# Board.net
KiCad netlist of a schematic drawn in EAGLE
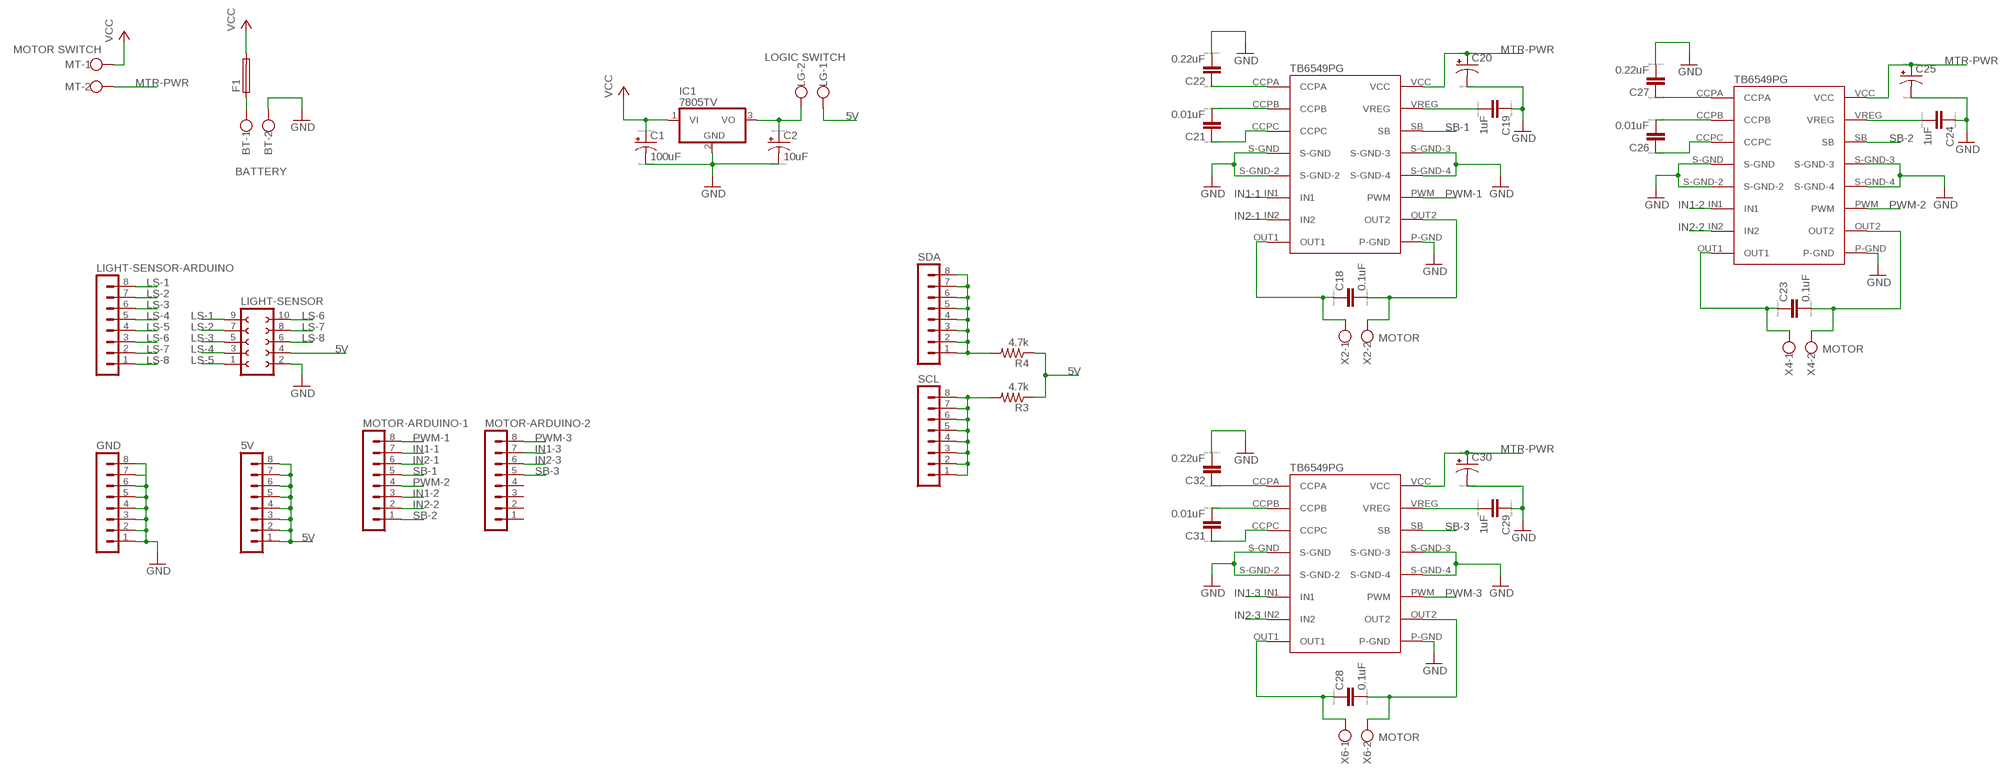
[diagram p0: schematic, sheet 1]

(export (version "E")
  (design (tool "Eeschema 10.0.6"))
  (components
    (comp (ref "5V")
      (value "MA08-1")
      (footprint "eagle-import:MA08-1")
      (libsource (lib "eagle-import") (part "MA08-1"))
    )
    (comp (ref "BT")
      (value "W237-102")
      (footprint "eagle-import:W237-102")
      (fields (field (name "MPN") "237-102"))
      (libsource (lib "eagle-import") (part "W237-102"))
    )
    (comp (ref "C1")
      (value "100uF")
      (footprint "eagle-import:E3,5-8")
      (libsource (lib "eagle-import") (part "CPOL-USE3.5-8"))
    )
    (comp (ref "C2")
      (value "10uF")
      (footprint "eagle-import:E3,5-8")
      (libsource (lib "eagle-import") (part "CPOL-USE3.5-8"))
    )
    (comp (ref "C18")
      (value "0.1uF")
      (footprint "eagle-import:YC7B5")
      (libsource (lib "eagle-import") (part "CYYC7B5"))
    )
    (comp (ref "C19")
      (value "1uF")
      (footprint "eagle-import:YC7B5")
      (libsource (lib "eagle-import") (part "CYYC7B5"))
    )
    (comp (ref "C20")
      (value "CPOL-USE3.5-8")
      (footprint "eagle-import:E3,5-8")
      (libsource (lib "eagle-import") (part "CPOL-USE3.5-8"))
    )
    (comp (ref "C21")
      (value "0.01uF")
      (footprint "eagle-import:YC7B5")
      (libsource (lib "eagle-import") (part "CYYC7B5"))
    )
    (comp (ref "C22")
      (value "0.22uF")
      (footprint "eagle-import:YC7B5")
      (libsource (lib "eagle-import") (part "CYYC7B5"))
    )
    (comp (ref "C23")
      (value "0.1uF")
      (footprint "eagle-import:YC7B5")
      (libsource (lib "eagle-import") (part "CYYC7B5"))
    )
    (comp (ref "C24")
      (value "1uF")
      (footprint "eagle-import:YC7B5")
      (libsource (lib "eagle-import") (part "CYYC7B5"))
    )
    (comp (ref "C25")
      (value "CPOL-USE3.5-8")
      (footprint "eagle-import:E3,5-8")
      (libsource (lib "eagle-import") (part "CPOL-USE3.5-8"))
    )
    (comp (ref "C26")
      (value "0.01uF")
      (footprint "eagle-import:YC7B5")
      (libsource (lib "eagle-import") (part "CYYC7B5"))
    )
    (comp (ref "C27")
      (value "0.22uF")
      (footprint "eagle-import:YC7B5")
      (libsource (lib "eagle-import") (part "CYYC7B5"))
    )
    (comp (ref "C28")
      (value "0.1uF")
      (footprint "eagle-import:YC7B5")
      (libsource (lib "eagle-import") (part "CYYC7B5"))
    )
    (comp (ref "C29")
      (value "1uF")
      (footprint "eagle-import:YC7B5")
      (libsource (lib "eagle-import") (part "CYYC7B5"))
    )
    (comp (ref "C30")
      (value "CPOL-USE3.5-8")
      (footprint "eagle-import:E3,5-8")
      (libsource (lib "eagle-import") (part "CPOL-USE3.5-8"))
    )
    (comp (ref "C31")
      (value "0.01uF")
      (footprint "eagle-import:YC7B5")
      (libsource (lib "eagle-import") (part "CYYC7B5"))
    )
    (comp (ref "C32")
      (value "0.22uF")
      (footprint "eagle-import:YC7B5")
      (libsource (lib "eagle-import") (part "CYYC7B5"))
    )
    (comp (ref "F1")
      (value "GSH15")
      (footprint "eagle-import:GSH15")
      (fields (field (name "MPN") "64900001039"))
      (libsource (lib "eagle-import") (part "GSH15"))
    )
    (comp (ref "GND")
      (value "MA08-1")
      (footprint "eagle-import:MA08-1")
      (libsource (lib "eagle-import") (part "MA08-1"))
    )
    (comp (ref "IC1")
      (value "7805TV")
      (footprint "eagle-import:TO220V")
      (libsource (lib "eagle-import") (part "78TV05"))
    )
    (comp (ref "LG")
      (value "W237-102")
      (footprint "eagle-import:W237-102")
      (fields (field (name "MPN") "237-102"))
      (libsource (lib "eagle-import") (part "W237-102"))
    )
    (comp (ref "LIGHT-SENSOR")
      (value "FE05-2")
      (footprint "eagle-import:FE05-2")
      (libsource (lib "eagle-import") (part "FE05-2"))
    )
    (comp (ref "LIGHT-SENSOR-ARDUINO")
      (value "MA08-1")
      (footprint "eagle-import:MA08-1")
      (libsource (lib "eagle-import") (part "MA08-1"))
    )
    (comp (ref "MOTOR-ARDUINO-1")
      (value "MA08-1")
      (footprint "eagle-import:MA08-1")
      (libsource (lib "eagle-import") (part "MA08-1"))
    )
    (comp (ref "MOTOR-ARDUINO-2")
      (value "MA08-1")
      (footprint "eagle-import:MA08-1")
      (libsource (lib "eagle-import") (part "MA08-1"))
    )
    (comp (ref "MT")
      (value "W237-102")
      (footprint "eagle-import:W237-102")
      (fields (field (name "MPN") "237-102"))
      (libsource (lib "eagle-import") (part "W237-102"))
    )
    (comp (ref "R3")
      (value "4.7k")
      (footprint "eagle-import:0207_10")
      (libsource (lib "eagle-import") (part "R-US_0207/10"))
    )
    (comp (ref "R4")
      (value "4.7k")
      (footprint "eagle-import:0207_10")
      (libsource (lib "eagle-import") (part "R-US_0207/10"))
    )
    (comp (ref "SCL")
      (value "MA08-1")
      (footprint "eagle-import:MA08-1")
      (libsource (lib "eagle-import") (part "MA08-1"))
    )
    (comp (ref "SDA")
      (value "MA08-1")
      (footprint "eagle-import:MA08-1")
      (libsource (lib "eagle-import") (part "MA08-1"))
    )
    (comp (ref "U$4")
      (value "TB6549PG")
      (footprint "eagle-import:TB6549PG")
      (libsource (lib "eagle-import") (part "TB6549PG"))
    )
    (comp (ref "U$5")
      (value "TB6549PG")
      (footprint "eagle-import:TB6549PG")
      (libsource (lib "eagle-import") (part "TB6549PG"))
    )
    (comp (ref "U$6")
      (value "TB6549PG")
      (footprint "eagle-import:TB6549PG")
      (libsource (lib "eagle-import") (part "TB6549PG"))
    )
    (comp (ref "X2")
      (value "W237-102")
      (footprint "eagle-import:W237-102")
      (fields (field (name "MPN") "237-102"))
      (libsource (lib "eagle-import") (part "W237-102"))
    )
    (comp (ref "X4")
      (value "W237-102")
      (footprint "eagle-import:W237-102")
      (fields (field (name "MPN") "237-102"))
      (libsource (lib "eagle-import") (part "W237-102"))
    )
    (comp (ref "X6")
      (value "W237-102")
      (footprint "eagle-import:W237-102")
      (fields (field (name "MPN") "237-102"))
      (libsource (lib "eagle-import") (part "W237-102"))
    )
  )
  (nets
    (net (code "1") (name "/5V") (class "Default")
      (node (ref "5V") (pin "1") (pinfunction "1_1") (pintype "passive"))
      (node (ref "5V") (pin "2") (pinfunction "2_2") (pintype "passive"))
      (node (ref "5V") (pin "3") (pinfunction "3_3") (pintype "passive"))
      (node (ref "5V") (pin "4") (pinfunction "4_4") (pintype "passive"))
      (node (ref "5V") (pin "5") (pinfunction "5_5") (pintype "passive"))
      (node (ref "5V") (pin "6") (pinfunction "6_6") (pintype "passive"))
      (node (ref "5V") (pin "7") (pinfunction "7_7") (pintype "passive"))
      (node (ref "5V") (pin "8") (pinfunction "8_8") (pintype "passive"))
      (node (ref "LG") (pin "1") (pinfunction "KL_1") (pintype "passive"))
      (node (ref "LIGHT-SENSOR") (pin "4") (pinfunction "4_4") (pintype "passive"))
      (node (ref "R3") (pin "1") (pinfunction "1_1") (pintype "passive"))
      (node (ref "R4") (pin "1") (pinfunction "1_1") (pintype "passive"))
    )
    (net (code "2") (name "/IN1-1") (class "Default")
      (node (ref "MOTOR-ARDUINO-1") (pin "7") (pinfunction "7_7") (pintype "passive"))
      (node (ref "U$4") (pin "IN1") (pinfunction "IN1_IN1") (pintype "bidirectional"))
    )
    (net (code "3") (name "/IN1-2") (class "Default")
      (node (ref "MOTOR-ARDUINO-1") (pin "3") (pinfunction "3_3") (pintype "passive"))
      (node (ref "U$5") (pin "IN1") (pinfunction "IN1_IN1") (pintype "bidirectional"))
    )
    (net (code "4") (name "/IN1-3") (class "Default")
      (node (ref "MOTOR-ARDUINO-2") (pin "7") (pinfunction "7_7") (pintype "passive"))
      (node (ref "U$6") (pin "IN1") (pinfunction "IN1_IN1") (pintype "bidirectional"))
    )
    (net (code "5") (name "/IN2-1") (class "Default")
      (node (ref "MOTOR-ARDUINO-1") (pin "6") (pinfunction "6_6") (pintype "passive"))
      (node (ref "U$4") (pin "IN2") (pinfunction "IN2_IN2") (pintype "bidirectional"))
    )
    (net (code "6") (name "/IN2-2") (class "Default")
      (node (ref "MOTOR-ARDUINO-1") (pin "2") (pinfunction "2_2") (pintype "passive"))
      (node (ref "U$5") (pin "IN2") (pinfunction "IN2_IN2") (pintype "bidirectional"))
    )
    (net (code "7") (name "/IN2-3") (class "Default")
      (node (ref "MOTOR-ARDUINO-2") (pin "6") (pinfunction "6_6") (pintype "passive"))
      (node (ref "U$6") (pin "IN2") (pinfunction "IN2_IN2") (pintype "bidirectional"))
    )
    (net (code "8") (name "/LS-1") (class "Default")
      (node (ref "LIGHT-SENSOR") (pin "9") (pinfunction "9_9") (pintype "passive"))
      (node (ref "LIGHT-SENSOR-ARDUINO") (pin "8") (pinfunction "8_8") (pintype "passive"))
    )
    (net (code "9") (name "/LS-2") (class "Default")
      (node (ref "LIGHT-SENSOR") (pin "7") (pinfunction "7_7") (pintype "passive"))
      (node (ref "LIGHT-SENSOR-ARDUINO") (pin "7") (pinfunction "7_7") (pintype "passive"))
    )
    (net (code "10") (name "/LS-3") (class "Default")
      (node (ref "LIGHT-SENSOR") (pin "5") (pinfunction "5_5") (pintype "passive"))
      (node (ref "LIGHT-SENSOR-ARDUINO") (pin "6") (pinfunction "6_6") (pintype "passive"))
    )
    (net (code "11") (name "/LS-4") (class "Default")
      (node (ref "LIGHT-SENSOR") (pin "3") (pinfunction "3_3") (pintype "passive"))
      (node (ref "LIGHT-SENSOR-ARDUINO") (pin "5") (pinfunction "5_5") (pintype "passive"))
    )
    (net (code "12") (name "/LS-5") (class "Default")
      (node (ref "LIGHT-SENSOR") (pin "1") (pinfunction "1_1") (pintype "passive"))
      (node (ref "LIGHT-SENSOR-ARDUINO") (pin "4") (pinfunction "4_4") (pintype "passive"))
    )
    (net (code "13") (name "/LS-6") (class "Default")
      (node (ref "LIGHT-SENSOR") (pin "10") (pinfunction "10_10") (pintype "passive"))
      (node (ref "LIGHT-SENSOR-ARDUINO") (pin "3") (pinfunction "3_3") (pintype "passive"))
    )
    (net (code "14") (name "/LS-7") (class "Default")
      (node (ref "LIGHT-SENSOR") (pin "8") (pinfunction "8_8") (pintype "passive"))
      (node (ref "LIGHT-SENSOR-ARDUINO") (pin "2") (pinfunction "2_2") (pintype "passive"))
    )
    (net (code "15") (name "/LS-8") (class "Default")
      (node (ref "LIGHT-SENSOR") (pin "6") (pinfunction "6_6") (pintype "passive"))
      (node (ref "LIGHT-SENSOR-ARDUINO") (pin "1") (pinfunction "1_1") (pintype "passive"))
    )
    (net (code "16") (name "/MTR-PWR") (class "Default")
      (node (ref "C20") (pin "+") (pinfunction "+_+") (pintype "passive"))
      (node (ref "C25") (pin "+") (pinfunction "+_+") (pintype "passive"))
      (node (ref "C30") (pin "+") (pinfunction "+_+") (pintype "passive"))
      (node (ref "MT") (pin "2") (pinfunction "KL_2") (pintype "passive"))
      (node (ref "U$4") (pin "VCC") (pinfunction "VCC_VCC") (pintype "bidirectional"))
      (node (ref "U$5") (pin "VCC") (pinfunction "VCC_VCC") (pintype "bidirectional"))
      (node (ref "U$6") (pin "VCC") (pinfunction "VCC_VCC") (pintype "bidirectional"))
    )
    (net (code "17") (name "/PWM-1") (class "Default")
      (node (ref "MOTOR-ARDUINO-1") (pin "8") (pinfunction "8_8") (pintype "passive"))
      (node (ref "U$4") (pin "PWM") (pinfunction "PWM_PWM") (pintype "bidirectional"))
    )
    (net (code "18") (name "/PWM-2") (class "Default")
      (node (ref "MOTOR-ARDUINO-1") (pin "4") (pinfunction "4_4") (pintype "passive"))
      (node (ref "U$5") (pin "PWM") (pinfunction "PWM_PWM") (pintype "bidirectional"))
    )
    (net (code "19") (name "/PWM-3") (class "Default")
      (node (ref "MOTOR-ARDUINO-2") (pin "8") (pinfunction "8_8") (pintype "passive"))
      (node (ref "U$6") (pin "PWM") (pinfunction "PWM_PWM") (pintype "bidirectional"))
    )
    (net (code "20") (name "/SB-1") (class "Default")
      (node (ref "MOTOR-ARDUINO-1") (pin "5") (pinfunction "5_5") (pintype "passive"))
      (node (ref "U$4") (pin "SB") (pinfunction "SB_SB") (pintype "bidirectional"))
    )
    (net (code "21") (name "/SB-2") (class "Default")
      (node (ref "MOTOR-ARDUINO-1") (pin "1") (pinfunction "1_1") (pintype "passive"))
      (node (ref "U$5") (pin "SB") (pinfunction "SB_SB") (pintype "bidirectional"))
    )
    (net (code "22") (name "/SB-3") (class "Default")
      (node (ref "MOTOR-ARDUINO-2") (pin "5") (pinfunction "5_5") (pintype "passive"))
      (node (ref "U$6") (pin "SB") (pinfunction "SB_SB") (pintype "bidirectional"))
    )
    (net (code "23") (name "GND") (class "Default")
      (node (ref "BT") (pin "2") (pinfunction "KL_2") (pintype "passive"))
      (node (ref "C1") (pin "-") (pinfunction "-_-") (pintype "passive"))
      (node (ref "C19") (pin "1") (pinfunction "1_1") (pintype "passive"))
      (node (ref "C2") (pin "-") (pinfunction "-_-") (pintype "passive"))
      (node (ref "C20") (pin "-") (pinfunction "-_-") (pintype "passive"))
      (node (ref "C22") (pin "2") (pinfunction "2_2") (pintype "passive"))
      (node (ref "C24") (pin "1") (pinfunction "1_1") (pintype "passive"))
      (node (ref "C25") (pin "-") (pinfunction "-_-") (pintype "passive"))
      (node (ref "C27") (pin "2") (pinfunction "2_2") (pintype "passive"))
      (node (ref "C29") (pin "1") (pinfunction "1_1") (pintype "passive"))
      (node (ref "C30") (pin "-") (pinfunction "-_-") (pintype "passive"))
      (node (ref "C32") (pin "2") (pinfunction "2_2") (pintype "passive"))
      (node (ref "GND") (pin "1") (pinfunction "1_1") (pintype "passive"))
      (node (ref "GND") (pin "2") (pinfunction "2_2") (pintype "passive"))
      (node (ref "GND") (pin "3") (pinfunction "3_3") (pintype "passive"))
      (node (ref "GND") (pin "4") (pinfunction "4_4") (pintype "passive"))
      (node (ref "GND") (pin "5") (pinfunction "5_5") (pintype "passive"))
      (node (ref "GND") (pin "6") (pinfunction "6_6") (pintype "passive"))
      (node (ref "GND") (pin "7") (pinfunction "7_7") (pintype "passive"))
      (node (ref "GND") (pin "8") (pinfunction "8_8") (pintype "passive"))
      (node (ref "IC1") (pin "2") (pinfunction "GND_2") (pintype "passive"))
      (node (ref "LIGHT-SENSOR") (pin "2") (pinfunction "2_2") (pintype "passive"))
      (node (ref "U$4") (pin "P-GND") (pinfunction "P-GND_P-GND") (pintype "bidirectional"))
      (node (ref "U$4") (pin "S-GND") (pinfunction "S-GND_S-GND") (pintype "bidirectional"))
      (node (ref "U$4") (pin "S-GND-2") (pinfunction "S-GND-2_S-GND-2") (pintype "bidirectional"))
      (node (ref "U$4") (pin "S-GND-3") (pinfunction "S-GND-3_S-GND-3") (pintype "bidirectional"))
      (node (ref "U$4") (pin "S-GND-4") (pinfunction "S-GND-4_S-GND-4") (pintype "bidirectional"))
      (node (ref "U$5") (pin "P-GND") (pinfunction "P-GND_P-GND") (pintype "bidirectional"))
      (node (ref "U$5") (pin "S-GND") (pinfunction "S-GND_S-GND") (pintype "bidirectional"))
      (node (ref "U$5") (pin "S-GND-2") (pinfunction "S-GND-2_S-GND-2") (pintype "bidirectional"))
      (node (ref "U$5") (pin "S-GND-3") (pinfunction "S-GND-3_S-GND-3") (pintype "bidirectional"))
      (node (ref "U$5") (pin "S-GND-4") (pinfunction "S-GND-4_S-GND-4") (pintype "bidirectional"))
      (node (ref "U$6") (pin "P-GND") (pinfunction "P-GND_P-GND") (pintype "bidirectional"))
      (node (ref "U$6") (pin "S-GND") (pinfunction "S-GND_S-GND") (pintype "bidirectional"))
      (node (ref "U$6") (pin "S-GND-2") (pinfunction "S-GND-2_S-GND-2") (pintype "bidirectional"))
      (node (ref "U$6") (pin "S-GND-3") (pinfunction "S-GND-3_S-GND-3") (pintype "bidirectional"))
      (node (ref "U$6") (pin "S-GND-4") (pinfunction "S-GND-4_S-GND-4") (pintype "bidirectional"))
    )
    (net (code "24") (name "Net-(BTA-KL)") (class "Default")
      (node (ref "BT") (pin "1") (pinfunction "KL_1") (pintype "passive"))
      (node (ref "F1") (pin "1") (pinfunction "1_1") (pintype "passive"))
    )
    (net (code "25") (name "Net-(C19-Pad2)") (class "Default")
      (node (ref "C19") (pin "2") (pinfunction "2_2") (pintype "passive"))
      (node (ref "U$4") (pin "VREG") (pinfunction "VREG_VREG") (pintype "bidirectional"))
    )
    (net (code "26") (name "Net-(C21-Pad1)") (class "Default")
      (node (ref "C21") (pin "1") (pinfunction "1_1") (pintype "passive"))
      (node (ref "U$4") (pin "CCPC") (pinfunction "CCPC_CCPC") (pintype "bidirectional"))
    )
    (net (code "27") (name "Net-(C21-Pad2)") (class "Default")
      (node (ref "C21") (pin "2") (pinfunction "2_2") (pintype "passive"))
      (node (ref "U$4") (pin "CCPB") (pinfunction "CCPB_CCPB") (pintype "bidirectional"))
    )
    (net (code "28") (name "Net-(C22-Pad1)") (class "Default")
      (node (ref "C22") (pin "1") (pinfunction "1_1") (pintype "passive"))
      (node (ref "U$4") (pin "CCPA") (pinfunction "CCPA_CCPA") (pintype "bidirectional"))
    )
    (net (code "29") (name "Net-(C24-Pad2)") (class "Default")
      (node (ref "C24") (pin "2") (pinfunction "2_2") (pintype "passive"))
      (node (ref "U$5") (pin "VREG") (pinfunction "VREG_VREG") (pintype "bidirectional"))
    )
    (net (code "30") (name "Net-(C26-Pad1)") (class "Default")
      (node (ref "C26") (pin "1") (pinfunction "1_1") (pintype "passive"))
      (node (ref "U$5") (pin "CCPC") (pinfunction "CCPC_CCPC") (pintype "bidirectional"))
    )
    (net (code "31") (name "Net-(C26-Pad2)") (class "Default")
      (node (ref "C26") (pin "2") (pinfunction "2_2") (pintype "passive"))
      (node (ref "U$5") (pin "CCPB") (pinfunction "CCPB_CCPB") (pintype "bidirectional"))
    )
    (net (code "32") (name "Net-(C27-Pad1)") (class "Default")
      (node (ref "C27") (pin "1") (pinfunction "1_1") (pintype "passive"))
      (node (ref "U$5") (pin "CCPA") (pinfunction "CCPA_CCPA") (pintype "bidirectional"))
    )
    (net (code "33") (name "Net-(C29-Pad2)") (class "Default")
      (node (ref "C29") (pin "2") (pinfunction "2_2") (pintype "passive"))
      (node (ref "U$6") (pin "VREG") (pinfunction "VREG_VREG") (pintype "bidirectional"))
    )
    (net (code "34") (name "Net-(C31-Pad1)") (class "Default")
      (node (ref "C31") (pin "1") (pinfunction "1_1") (pintype "passive"))
      (node (ref "U$6") (pin "CCPC") (pinfunction "CCPC_CCPC") (pintype "bidirectional"))
    )
    (net (code "35") (name "Net-(C31-Pad2)") (class "Default")
      (node (ref "C31") (pin "2") (pinfunction "2_2") (pintype "passive"))
      (node (ref "U$6") (pin "CCPB") (pinfunction "CCPB_CCPB") (pintype "bidirectional"))
    )
    (net (code "36") (name "Net-(C32-Pad1)") (class "Default")
      (node (ref "C32") (pin "1") (pinfunction "1_1") (pintype "passive"))
      (node (ref "U$6") (pin "CCPA") (pinfunction "CCPA_CCPA") (pintype "bidirectional"))
    )
    (net (code "37") (name "Net-(IC1-VO)") (class "Default")
      (node (ref "C2") (pin "+") (pinfunction "+_+") (pintype "passive"))
      (node (ref "IC1") (pin "3") (pinfunction "VO_3") (pintype "passive"))
      (node (ref "LG") (pin "2") (pinfunction "KL_2") (pintype "passive"))
    )
    (net (code "38") (name "Net-(R3-Pad2)") (class "Default")
      (node (ref "R3") (pin "2") (pinfunction "2_2") (pintype "passive"))
      (node (ref "SCL") (pin "1") (pinfunction "1_1") (pintype "passive"))
      (node (ref "SCL") (pin "2") (pinfunction "2_2") (pintype "passive"))
      (node (ref "SCL") (pin "3") (pinfunction "3_3") (pintype "passive"))
      (node (ref "SCL") (pin "4") (pinfunction "4_4") (pintype "passive"))
      (node (ref "SCL") (pin "5") (pinfunction "5_5") (pintype "passive"))
      (node (ref "SCL") (pin "6") (pinfunction "6_6") (pintype "passive"))
      (node (ref "SCL") (pin "7") (pinfunction "7_7") (pintype "passive"))
      (node (ref "SCL") (pin "8") (pinfunction "8_8") (pintype "passive"))
    )
    (net (code "39") (name "Net-(R4-Pad2)") (class "Default")
      (node (ref "R4") (pin "2") (pinfunction "2_2") (pintype "passive"))
      (node (ref "SDA") (pin "1") (pinfunction "1_1") (pintype "passive"))
      (node (ref "SDA") (pin "2") (pinfunction "2_2") (pintype "passive"))
      (node (ref "SDA") (pin "3") (pinfunction "3_3") (pintype "passive"))
      (node (ref "SDA") (pin "4") (pinfunction "4_4") (pintype "passive"))
      (node (ref "SDA") (pin "5") (pinfunction "5_5") (pintype "passive"))
      (node (ref "SDA") (pin "6") (pinfunction "6_6") (pintype "passive"))
      (node (ref "SDA") (pin "7") (pinfunction "7_7") (pintype "passive"))
      (node (ref "SDA") (pin "8") (pinfunction "8_8") (pintype "passive"))
    )
    (net (code "40") (name "Net-(X2A-KL)") (class "Default")
      (node (ref "C18") (pin "1") (pinfunction "1_1") (pintype "passive"))
      (node (ref "U$4") (pin "OUT1") (pinfunction "OUT1_OUT1") (pintype "bidirectional"))
      (node (ref "X2") (pin "1") (pinfunction "KL_1") (pintype "passive"))
    )
    (net (code "41") (name "Net-(X2B-KL)") (class "Default")
      (node (ref "C18") (pin "2") (pinfunction "2_2") (pintype "passive"))
      (node (ref "U$4") (pin "OUT2") (pinfunction "OUT2_OUT2") (pintype "bidirectional"))
      (node (ref "X2") (pin "2") (pinfunction "KL_2") (pintype "passive"))
    )
    (net (code "42") (name "Net-(X4A-KL)") (class "Default")
      (node (ref "C23") (pin "1") (pinfunction "1_1") (pintype "passive"))
      (node (ref "U$5") (pin "OUT1") (pinfunction "OUT1_OUT1") (pintype "bidirectional"))
      (node (ref "X4") (pin "1") (pinfunction "KL_1") (pintype "passive"))
    )
    (net (code "43") (name "Net-(X4B-KL)") (class "Default")
      (node (ref "C23") (pin "2") (pinfunction "2_2") (pintype "passive"))
      (node (ref "U$5") (pin "OUT2") (pinfunction "OUT2_OUT2") (pintype "bidirectional"))
      (node (ref "X4") (pin "2") (pinfunction "KL_2") (pintype "passive"))
    )
    (net (code "44") (name "Net-(X6A-KL)") (class "Default")
      (node (ref "C28") (pin "1") (pinfunction "1_1") (pintype "passive"))
      (node (ref "U$6") (pin "OUT1") (pinfunction "OUT1_OUT1") (pintype "bidirectional"))
      (node (ref "X6") (pin "1") (pinfunction "KL_1") (pintype "passive"))
    )
    (net (code "45") (name "Net-(X6B-KL)") (class "Default")
      (node (ref "C28") (pin "2") (pinfunction "2_2") (pintype "passive"))
      (node (ref "U$6") (pin "OUT2") (pinfunction "OUT2_OUT2") (pintype "bidirectional"))
      (node (ref "X6") (pin "2") (pinfunction "KL_2") (pintype "passive"))
    )
    (net (code "46") (name "VCC") (class "Default")
      (node (ref "C1") (pin "+") (pinfunction "+_+") (pintype "passive"))
      (node (ref "F1") (pin "2") (pinfunction "2_2") (pintype "passive"))
      (node (ref "IC1") (pin "1") (pinfunction "VI_1") (pintype "input"))
      (node (ref "MT") (pin "1") (pinfunction "KL_1") (pintype "passive"))
    )
    (net (code "47") (name "unconnected-(MOTOR-ARDUINO-2-Pad1)") (class "Default")
      (node (ref "MOTOR-ARDUINO-2") (pin "1") (pinfunction "1_1") (pintype "passive"))
    )
    (net (code "48") (name "unconnected-(MOTOR-ARDUINO-2-Pad2)") (class "Default")
      (node (ref "MOTOR-ARDUINO-2") (pin "2") (pinfunction "2_2") (pintype "passive"))
    )
    (net (code "49") (name "unconnected-(MOTOR-ARDUINO-2-Pad3)") (class "Default")
      (node (ref "MOTOR-ARDUINO-2") (pin "3") (pinfunction "3_3") (pintype "passive"))
    )
    (net (code "50") (name "unconnected-(MOTOR-ARDUINO-2-Pad4)") (class "Default")
      (node (ref "MOTOR-ARDUINO-2") (pin "4") (pinfunction "4_4") (pintype "passive"))
    )
  )
)
